# power.net
KiCad netlist of a schematic drawn in Altium Designer
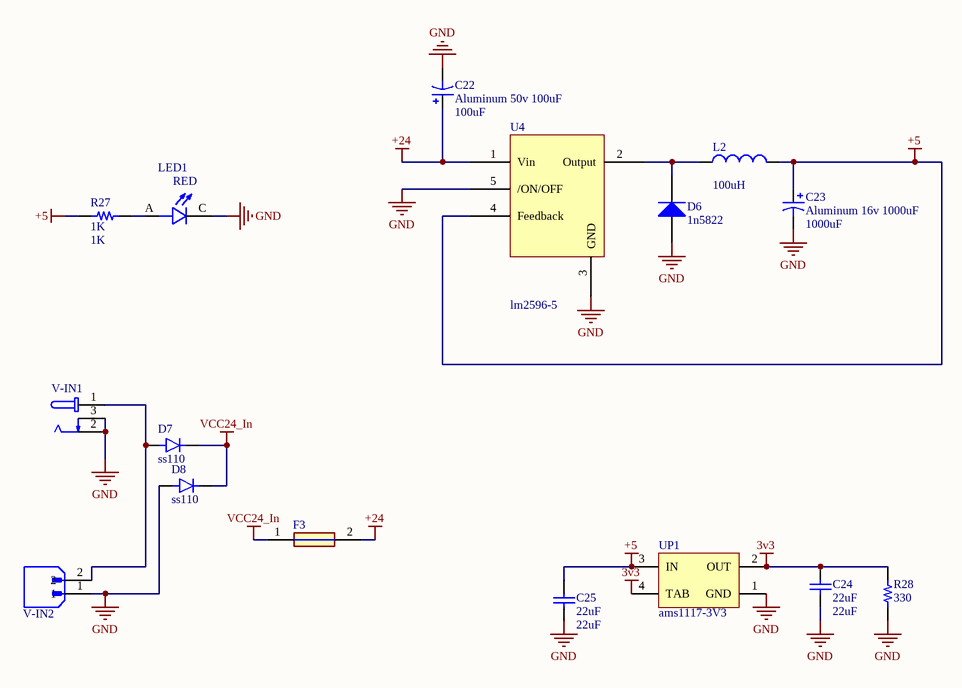
[diagram p0: power.SchDoc]

(export (version "E")
  (design (tool "Eeschema 10.0.6"))
  (components
    (comp (ref "C22")
      (value "Aluminum 50v 100uF")
      (footprint "Cap SMD 100UF 35~50v")
      (description "CAP POLAR SMD")
      (fields (field (name "ALTIUM_VALUE") "100uF") (field (name "PUBLISHER") "Altium Limited"))
      (libsource (lib "Miscellaneous Devices") (part "Cap Pol1"))
    )
    (comp (ref "C23")
      (value "Aluminum 16v 1000uF")
      (footprint "CAP SMD 1000UF 16V")
      (description "CAP POLAR SMD")
      (fields (field (name "ALTIUM_VALUE") "1000uF") (field (name "PUBLISHER") "Altium Limited"))
      (libsource (lib "Miscellaneous Devices") (part "Cap Pol1"))
    )
    (comp (ref "C24")
      (value "22uF")
      (footprint "0603C")
      (description "CAP SMD 0603")
      (fields (field (name "ALTIUM_VALUE") "22uF") (field (name "PUBLISHER") "Altium Limited"))
      (libsource (lib "Miscellaneous Devices") (part "Cap"))
    )
    (comp (ref "C25")
      (value "22uF")
      (footprint "0603C")
      (description "CAP SMD 0603")
      (fields (field (name "ALTIUM_VALUE") "22uF") (field (name "PUBLISHER") "Altium Limited"))
      (libsource (lib "Miscellaneous Devices") (part "Cap"))
    )
    (comp (ref "D6")
      (value "1n5822")
      (footprint "SMA DIODE 2")
      (description "1 Amp schottky Diode SMA")
      (fields (field (name "PUBLISHER") "Altium Limited"))
      (libsource (lib "Miscellaneous Devices") (part "Diode 1N4007"))
    )
    (comp (ref "D7")
      (value "ss110")
      (footprint "ss110")
      (description "Diode Super Barrier 60V 500mA Surface Mount SOD-123")
      (fields (field (name "MP") "SBR0560S1-7") (field (name "MF") "Diodes Inc."))
      (libsource (lib "diode") (part "SBR0560S1-7"))
    )
    (comp (ref "D8")
      (value "ss110")
      (footprint "ss110")
      (description "Diode Super Barrier 60V 500mA Surface Mount SOD-123")
      (fields (field (name "MP") "SBR0560S1-7") (field (name "MF") "Diodes Inc."))
      (libsource (lib "diode") (part "SBR0560S1-7"))
    )
    (comp (ref "F3")
      (value "fuse 2amp")
      (footprint "1206 FUSE")
      (description "Fuse 1206")
      (fields (field (name "MANUFACTURER_PART_NUMBER") "1206SFS200F/63-2"))
      (libsource (lib "robot1") (part "1206SFS200F_63-2"))
    )
    (comp (ref "L2")
      (value "100uH")
      (footprint "inductor")
      (description "Inductor 12*12mm")
      (fields (field (name "Comment") "inductor 100uH") (field (name "PUBLISHER") "Altium Limited"))
      (libsource (lib "Miscellaneous Devices") (part "Inductor"))
    )
    (comp (ref "LED1")
      (value "LED RED")
      (footprint "LED_7012X1")
      (description "LED SMD 0805 RED")
      (fields (field (name "MP") "7012X1"))
      (libsource (lib "LED0805") (part "7012X1"))
    )
    (comp (ref "R27")
      (value "1K")
      (footprint "0603R")
      (description "RES SMD 0603")
      (fields (field (name "PART NUMBER") "RCS0805100KFKEA") (field (name "ALTIUM_VALUE") "1K"))
      (libsource (lib "lamp control-ver2") (part "Resistor"))
    )
    (comp (ref "R28")
      (value "330")
      (footprint "0603R")
      (description "RES SMD 0603")
      (fields (field (name "PART NUMBER") "RCS0805100KFKEA"))
      (libsource (lib "lamp control-ver2") (part "Resistor"))
    )
    (comp (ref "U4") (value "lm2596-5") (footprint "2596") (libsource (lib "No.2") (part "lm2596")))
    (comp (ref "UP1")
      (value "ams1117-3V3")
      (footprint "SOT223")
      (description "3.3 Volt, 800mA SOT-223")
      (fields (field (name "DESIGNER") "Ali Hafizi"))
      (libsource (lib "Altium (2)") (part "AMS1117-x.x"))
    )
    (comp (ref "V-IN1")
      (value "DC jack power")
      (footprint "GCT_DCJ235-05-A-XX-X_REVA")
      (description "Dc Power Jack on-board")
      (fields (field (name "MF") "Global Connector Technology") (field (name "MP") "DCJ235-05-A-K1-A"))
      (libsource (lib "DCJ235-05-A-XX-X_REVA") (part "DCJ235-05-A-XX-X_REVA"))
    )
    (comp (ref "V-IN2")
      (value "Phoenix")
      (footprint "AMPHENOL_OQ0271510000G")
      (description "Phoenix Terminal Right 2PIN")
      (fields (field (name "MP") "OQ0271510000G") (field (name "MF") "Amphenol Anytek"))
      (libsource (lib "phoenix2") (part "OQ0271510000G"))
    )
  )
  (nets
    (net (code "1") (name "+5") (class "Default")
      (node (ref "C23") (pin "1") (pinfunction "1_1") (pintype "passive"))
      (node (ref "C25") (pin "2") (pinfunction "2_2") (pintype "passive"))
      (node (ref "L2") (pin "2") (pinfunction "2_2") (pintype "passive"))
      (node (ref "R27") (pin "1") (pinfunction "1_1") (pintype "passive"))
      (node (ref "U4") (pin "4") (pinfunction "Feedback_4") (pintype "power_in"))
      (node (ref "UP1") (pin "3") (pinfunction "IN_3") (pintype "power_in"))
    )
    (net (code "2") (name "+24") (class "Default")
      (node (ref "C22") (pin "1") (pinfunction "1_1") (pintype "passive"))
      (node (ref "F3") (pin "2") (pinfunction "2_2") (pintype "passive"))
      (node (ref "U4") (pin "1") (pinfunction "Vin_1") (pintype "power_in"))
    )
    (net (code "3") (name "3v3") (class "Default")
      (node (ref "C24") (pin "2") (pinfunction "2_2") (pintype "passive"))
      (node (ref "R28") (pin "1") (pinfunction "1_1") (pintype "passive"))
      (node (ref "UP1") (pin "2") (pinfunction "OUT_2") (pintype "power_in"))
      (node (ref "UP1") (pin "4") (pinfunction "TAB_4") (pintype "power_in"))
    )
    (net (code "4") (name "GND") (class "Default")
      (node (ref "C22") (pin "2") (pinfunction "2_2") (pintype "passive"))
      (node (ref "C23") (pin "2") (pinfunction "2_2") (pintype "passive"))
      (node (ref "C24") (pin "1") (pinfunction "1_1") (pintype "passive"))
      (node (ref "C25") (pin "1") (pinfunction "1_1") (pintype "passive"))
      (node (ref "D6") (pin "1") (pinfunction "A_1") (pintype "passive"))
      (node (ref "D8") (pin "A") (pinfunction "A_A") (pintype "passive"))
      (node (ref "LED1") (pin "C") (pinfunction "C_C") (pintype "passive"))
      (node (ref "R28") (pin "2") (pinfunction "2_2") (pintype "passive"))
      (node (ref "U4") (pin "3") (pinfunction "GND_3") (pintype "power_in"))
      (node (ref "U4") (pin "5") (pinfunction "/ON/OFF_5") (pintype "power_in"))
      (node (ref "UP1") (pin "1") (pinfunction "GND_1") (pintype "power_in"))
      (node (ref "V-IN1") (pin "2") (pinfunction "2_2") (pintype "passive"))
      (node (ref "V-IN1") (pin "3") (pinfunction "3_3") (pintype "passive"))
      (node (ref "V-IN2") (pin "1") (pinfunction "1_1") (pintype "passive"))
    )
    (net (code "5") (name "Net-(D6-K)") (class "Default")
      (node (ref "D6") (pin "2") (pinfunction "K_2") (pintype "passive"))
      (node (ref "L2") (pin "1") (pinfunction "1_1") (pintype "passive"))
      (node (ref "U4") (pin "2") (pinfunction "Output_2") (pintype "power_in"))
    )
    (net (code "6") (name "Net-(D7-PadA)") (class "Default")
      (node (ref "D7") (pin "A") (pinfunction "A_A") (pintype "passive"))
      (node (ref "V-IN1") (pin "1") (pinfunction "1_1") (pintype "passive"))
      (node (ref "V-IN2") (pin "2") (pinfunction "2_2") (pintype "passive"))
    )
    (net (code "7") (name "Net-(LED1-PadA)") (class "Default")
      (node (ref "LED1") (pin "A") (pinfunction "A_A") (pintype "passive"))
      (node (ref "R27") (pin "2") (pinfunction "2_2") (pintype "passive"))
    )
    (net (code "8") (name "VCC24_In") (class "Default")
      (node (ref "D7") (pin "C") (pinfunction "K_C") (pintype "passive"))
      (node (ref "D8") (pin "C") (pinfunction "K_C") (pintype "passive"))
      (node (ref "F3") (pin "1") (pinfunction "1_1") (pintype "passive"))
    )
  )
)
